# Power.net
KiCad netlist of a schematic drawn in EAGLE
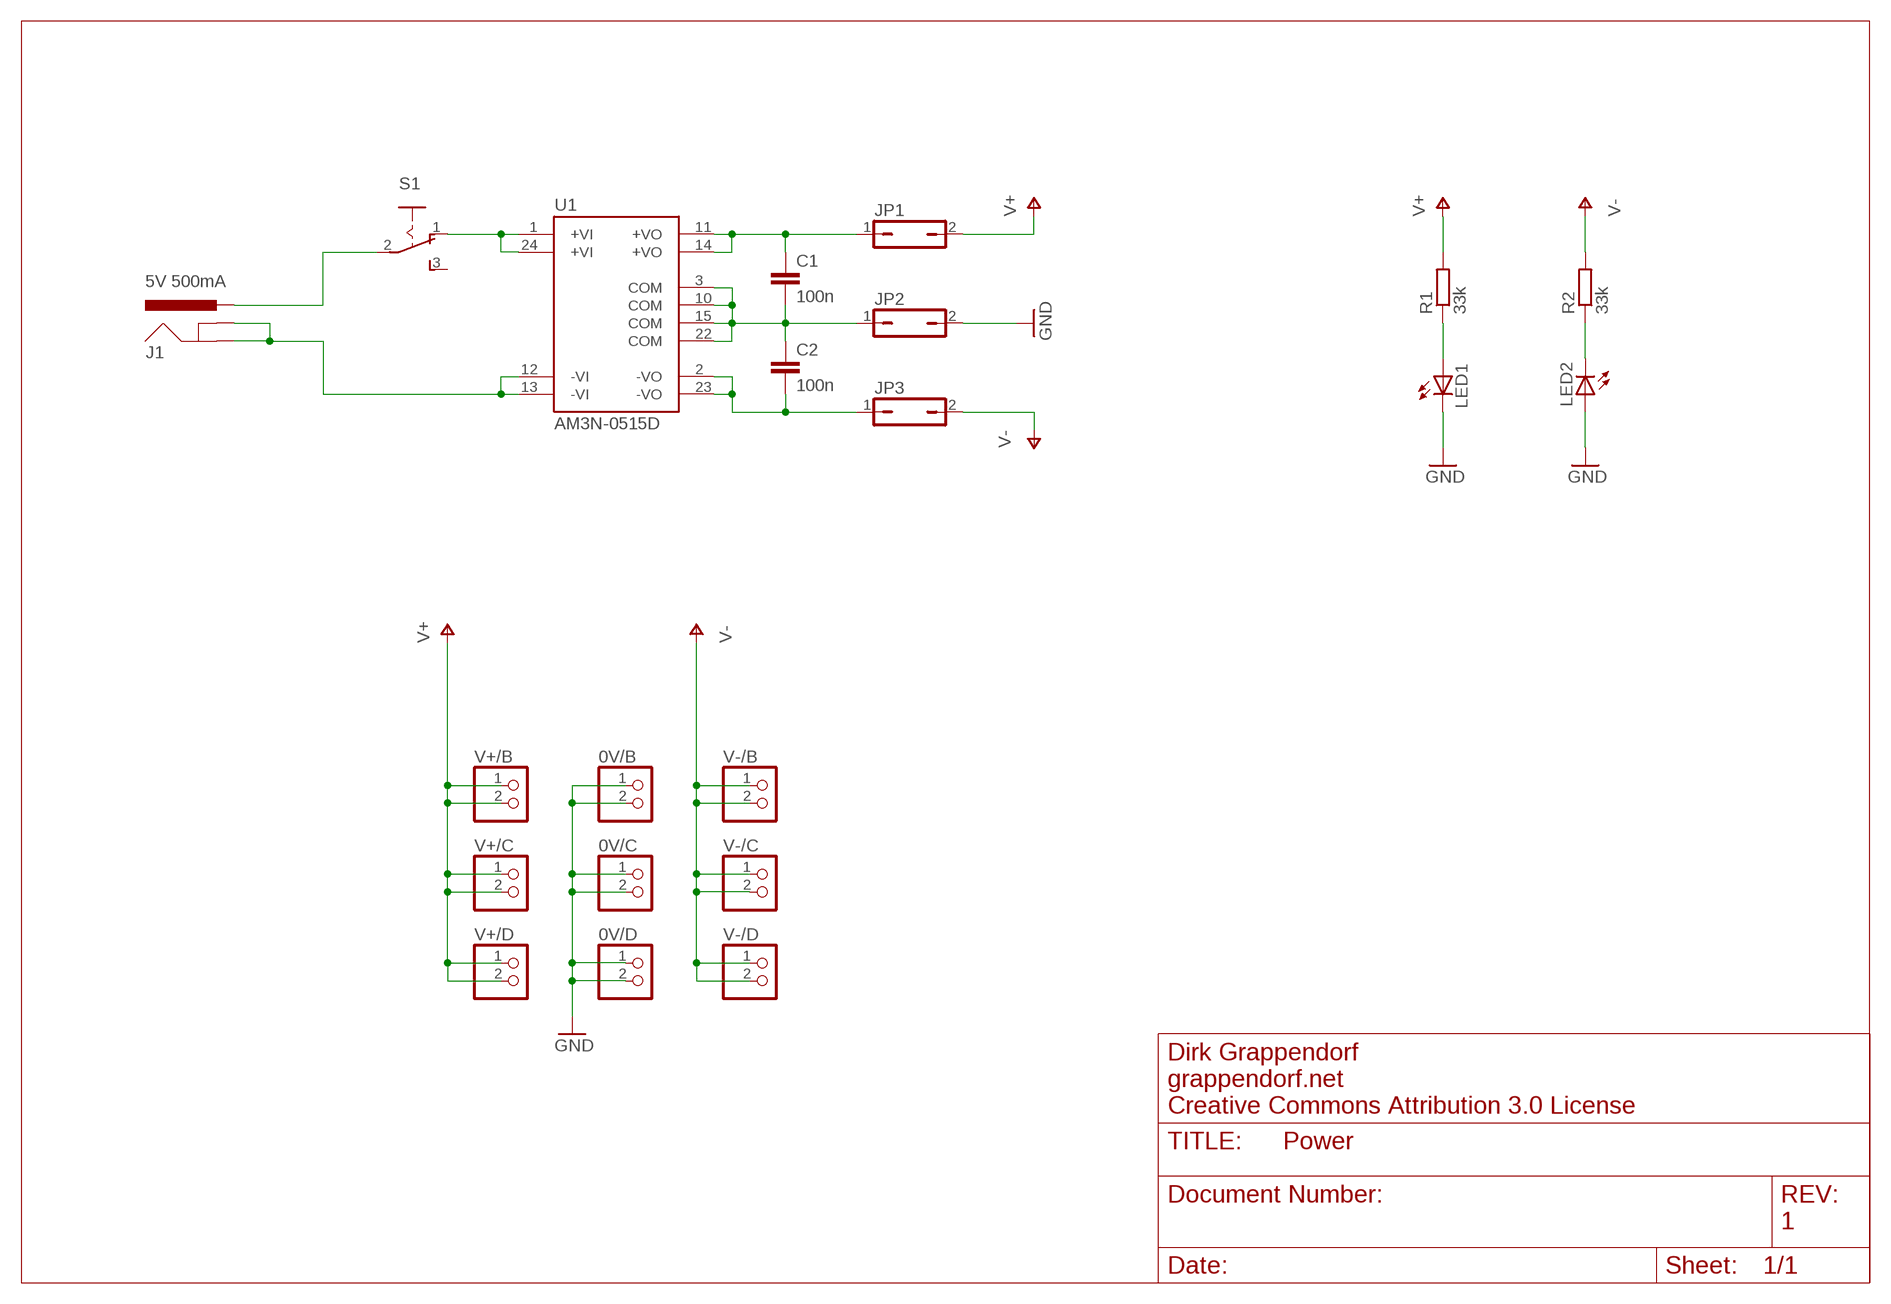
[diagram p0: schematic, sheet 1]

(export (version "E")
  (design (tool "Eeschema 10.0.6"))
  (components
    (comp (ref "0V/B")
      (value "PINHD-1X2")
      (footprint "eagle-import:1X02")
      (libsource (lib "eagle-import") (part "PINHD-1X2"))
    )
    (comp (ref "0V/C")
      (value "PINHD-1X2")
      (footprint "eagle-import:1X02")
      (libsource (lib "eagle-import") (part "PINHD-1X2"))
    )
    (comp (ref "0V/D")
      (value "PINHD-1X2")
      (footprint "eagle-import:1X02")
      (libsource (lib "eagle-import") (part "PINHD-1X2"))
    )
    (comp (ref "C1")
      (value "100n")
      (footprint "eagle-import:C025-025X050")
      (libsource (lib "eagle-import") (part "C-EU025-025X050"))
    )
    (comp (ref "C2")
      (value "100n")
      (footprint "eagle-import:C025-025X050")
      (libsource (lib "eagle-import") (part "C-EU025-025X050"))
    )
    (comp (ref "J1")
      (value "5V 500mA")
      (footprint "eagle-import:POWER_JACK_PTH")
      (libsource (lib "eagle-import") (part "POWER_JACKPTH"))
    )
    (comp (ref "JP1")
      (value "JP1Q")
      (footprint "eagle-import:JP1")
      (libsource (lib "eagle-import") (part "JP1Q"))
    )
    (comp (ref "JP2")
      (value "JP1Q")
      (footprint "eagle-import:JP1")
      (libsource (lib "eagle-import") (part "JP1Q"))
    )
    (comp (ref "JP3")
      (value "JP1Q")
      (footprint "eagle-import:JP1")
      (libsource (lib "eagle-import") (part "JP1Q"))
    )
    (comp (ref "LED1")
      (value "LED3MM")
      (footprint "eagle-import:LED3MM")
      (libsource (lib "eagle-import") (part "LED3MM"))
    )
    (comp (ref "LED2")
      (value "LED3MM")
      (footprint "eagle-import:LED3MM")
      (libsource (lib "eagle-import") (part "LED3MM"))
    )
    (comp (ref "R1")
      (value "33k")
      (footprint "eagle-import:0207_7")
      (libsource (lib "eagle-import") (part "R-EU_0207/7"))
    )
    (comp (ref "R2")
      (value "33k")
      (footprint "eagle-import:0207_7")
      (libsource (lib "eagle-import") (part "R-EU_0207/7"))
    )
    (comp (ref "S1")
      (value "REICHELT-SS_13ASP")
      (footprint "eagle-import:REICHELT-SS_13ASP")
      (libsource (lib "eagle-import") (part "REICHELT-SS_13ASP"))
    )
    (comp (ref "U1")
      (value "AM3N-0515D")
      (footprint "eagle-import:AM3N_DIL24")
      (libsource (lib "eagle-import") (part "AM3N-D0515"))
    )
    (comp (ref "V+/B")
      (value "PINHD-1X2")
      (footprint "eagle-import:1X02")
      (libsource (lib "eagle-import") (part "PINHD-1X2"))
    )
    (comp (ref "V+/C")
      (value "PINHD-1X2")
      (footprint "eagle-import:1X02")
      (libsource (lib "eagle-import") (part "PINHD-1X2"))
    )
    (comp (ref "V+/D")
      (value "PINHD-1X2")
      (footprint "eagle-import:1X02")
      (libsource (lib "eagle-import") (part "PINHD-1X2"))
    )
    (comp (ref "V-/B")
      (value "PINHD-1X2")
      (footprint "eagle-import:1X02")
      (libsource (lib "eagle-import") (part "PINHD-1X2"))
    )
    (comp (ref "V-/C")
      (value "PINHD-1X2")
      (footprint "eagle-import:1X02")
      (libsource (lib "eagle-import") (part "PINHD-1X2"))
    )
    (comp (ref "V-/D")
      (value "PINHD-1X2")
      (footprint "eagle-import:1X02")
      (libsource (lib "eagle-import") (part "PINHD-1X2"))
    )
  )
  (nets
    (net (code "1") (name "GND") (class "Default")
      (node (ref "0V/B") (pin "1") (pinfunction "1_1") (pintype "passive"))
      (node (ref "0V/B") (pin "2") (pinfunction "2_2") (pintype "passive"))
      (node (ref "0V/C") (pin "1") (pinfunction "1_1") (pintype "passive"))
      (node (ref "0V/C") (pin "2") (pinfunction "2_2") (pintype "passive"))
      (node (ref "0V/D") (pin "1") (pinfunction "1_1") (pintype "passive"))
      (node (ref "0V/D") (pin "2") (pinfunction "2_2") (pintype "passive"))
      (node (ref "JP2") (pin "2") (pinfunction "2_2") (pintype "passive"))
      (node (ref "LED1") (pin "K") (pinfunction "C_K") (pintype "passive"))
      (node (ref "LED2") (pin "A") (pinfunction "A_A") (pintype "passive"))
    )
    (net (code "2") (name "Net-(C1-Pad1)") (class "Default")
      (node (ref "C1") (pin "1") (pinfunction "1_1") (pintype "passive"))
      (node (ref "JP1") (pin "1") (pinfunction "1_1") (pintype "passive"))
      (node (ref "U1") (pin "11") (pinfunction "+VO_11") (pintype "power_in"))
      (node (ref "U1") (pin "14") (pinfunction "+VO_14") (pintype "power_in"))
    )
    (net (code "3") (name "Net-(C1-Pad2)") (class "Default")
      (node (ref "C1") (pin "2") (pinfunction "2_2") (pintype "passive"))
      (node (ref "C2") (pin "1") (pinfunction "1_1") (pintype "passive"))
      (node (ref "JP2") (pin "1") (pinfunction "1_1") (pintype "passive"))
      (node (ref "U1") (pin "10") (pinfunction "COM_10") (pintype "power_in"))
      (node (ref "U1") (pin "15") (pinfunction "COM_15") (pintype "power_in"))
      (node (ref "U1") (pin "22") (pinfunction "COM_22") (pintype "power_in"))
      (node (ref "U1") (pin "3") (pinfunction "COM_3") (pintype "power_in"))
    )
    (net (code "4") (name "Net-(C2-Pad2)") (class "Default")
      (node (ref "C2") (pin "2") (pinfunction "2_2") (pintype "passive"))
      (node (ref "JP3") (pin "1") (pinfunction "1_1") (pintype "passive"))
      (node (ref "U1") (pin "2") (pinfunction "-VO_2") (pintype "power_in"))
      (node (ref "U1") (pin "23") (pinfunction "-VO_23") (pintype "power_in"))
    )
    (net (code "5") (name "Net-(J1-PadGND)") (class "Default")
      (node (ref "J1") (pin "GND") (pinfunction "GND_GND") (pintype "bidirectional"))
      (node (ref "J1") (pin "GNDBREAK") (pinfunction "GNDBREAK_GNDBREAK") (pintype "bidirectional"))
      (node (ref "U1") (pin "12") (pinfunction "-VI_12") (pintype "power_in"))
      (node (ref "U1") (pin "13") (pinfunction "-VI_13") (pintype "power_in"))
    )
    (net (code "6") (name "Net-(LED1-PadA)") (class "Default")
      (node (ref "LED1") (pin "A") (pinfunction "A_A") (pintype "passive"))
      (node (ref "R1") (pin "1") (pinfunction "1_1") (pintype "passive"))
    )
    (net (code "7") (name "Net-(LED2-C)") (class "Default")
      (node (ref "LED2") (pin "K") (pinfunction "C_K") (pintype "passive"))
      (node (ref "R2") (pin "1") (pinfunction "1_1") (pintype "passive"))
    )
    (net (code "8") (name "Net-(S1-O)") (class "Default")
      (node (ref "S1") (pin "1") (pinfunction "O_1") (pintype "passive"))
      (node (ref "U1") (pin "1") (pinfunction "+VI_1") (pintype "power_in"))
      (node (ref "U1") (pin "24") (pinfunction "+VI_24") (pintype "power_in"))
    )
    (net (code "9") (name "Net-(S1-P)") (class "Default")
      (node (ref "J1") (pin "PWR") (pinfunction "PWR_PWR") (pintype "bidirectional"))
      (node (ref "S1") (pin "2") (pinfunction "P_2") (pintype "passive"))
    )
    (net (code "10") (name "V+") (class "Default")
      (node (ref "JP1") (pin "2") (pinfunction "2_2") (pintype "passive"))
      (node (ref "R1") (pin "2") (pinfunction "2_2") (pintype "passive"))
      (node (ref "V+/B") (pin "1") (pinfunction "1_1") (pintype "passive"))
      (node (ref "V+/B") (pin "2") (pinfunction "2_2") (pintype "passive"))
      (node (ref "V+/C") (pin "1") (pinfunction "1_1") (pintype "passive"))
      (node (ref "V+/C") (pin "2") (pinfunction "2_2") (pintype "passive"))
      (node (ref "V+/D") (pin "1") (pinfunction "1_1") (pintype "passive"))
      (node (ref "V+/D") (pin "2") (pinfunction "2_2") (pintype "passive"))
    )
    (net (code "11") (name "V-") (class "Default")
      (node (ref "JP3") (pin "2") (pinfunction "2_2") (pintype "passive"))
      (node (ref "R2") (pin "2") (pinfunction "2_2") (pintype "passive"))
      (node (ref "V-/B") (pin "1") (pinfunction "1_1") (pintype "passive"))
      (node (ref "V-/B") (pin "2") (pinfunction "2_2") (pintype "passive"))
      (node (ref "V-/C") (pin "1") (pinfunction "1_1") (pintype "passive"))
      (node (ref "V-/C") (pin "2") (pinfunction "2_2") (pintype "passive"))
      (node (ref "V-/D") (pin "1") (pinfunction "1_1") (pintype "passive"))
      (node (ref "V-/D") (pin "2") (pinfunction "2_2") (pintype "passive"))
    )
    (net (code "12") (name "unconnected-(S1-S-Pad3)") (class "Default")
      (node (ref "S1") (pin "3") (pinfunction "S_3") (pintype "passive"))
    )
  )
)
